# EVmulator_T85_Compact.net
KiCad netlist of a schematic drawn in EAGLE
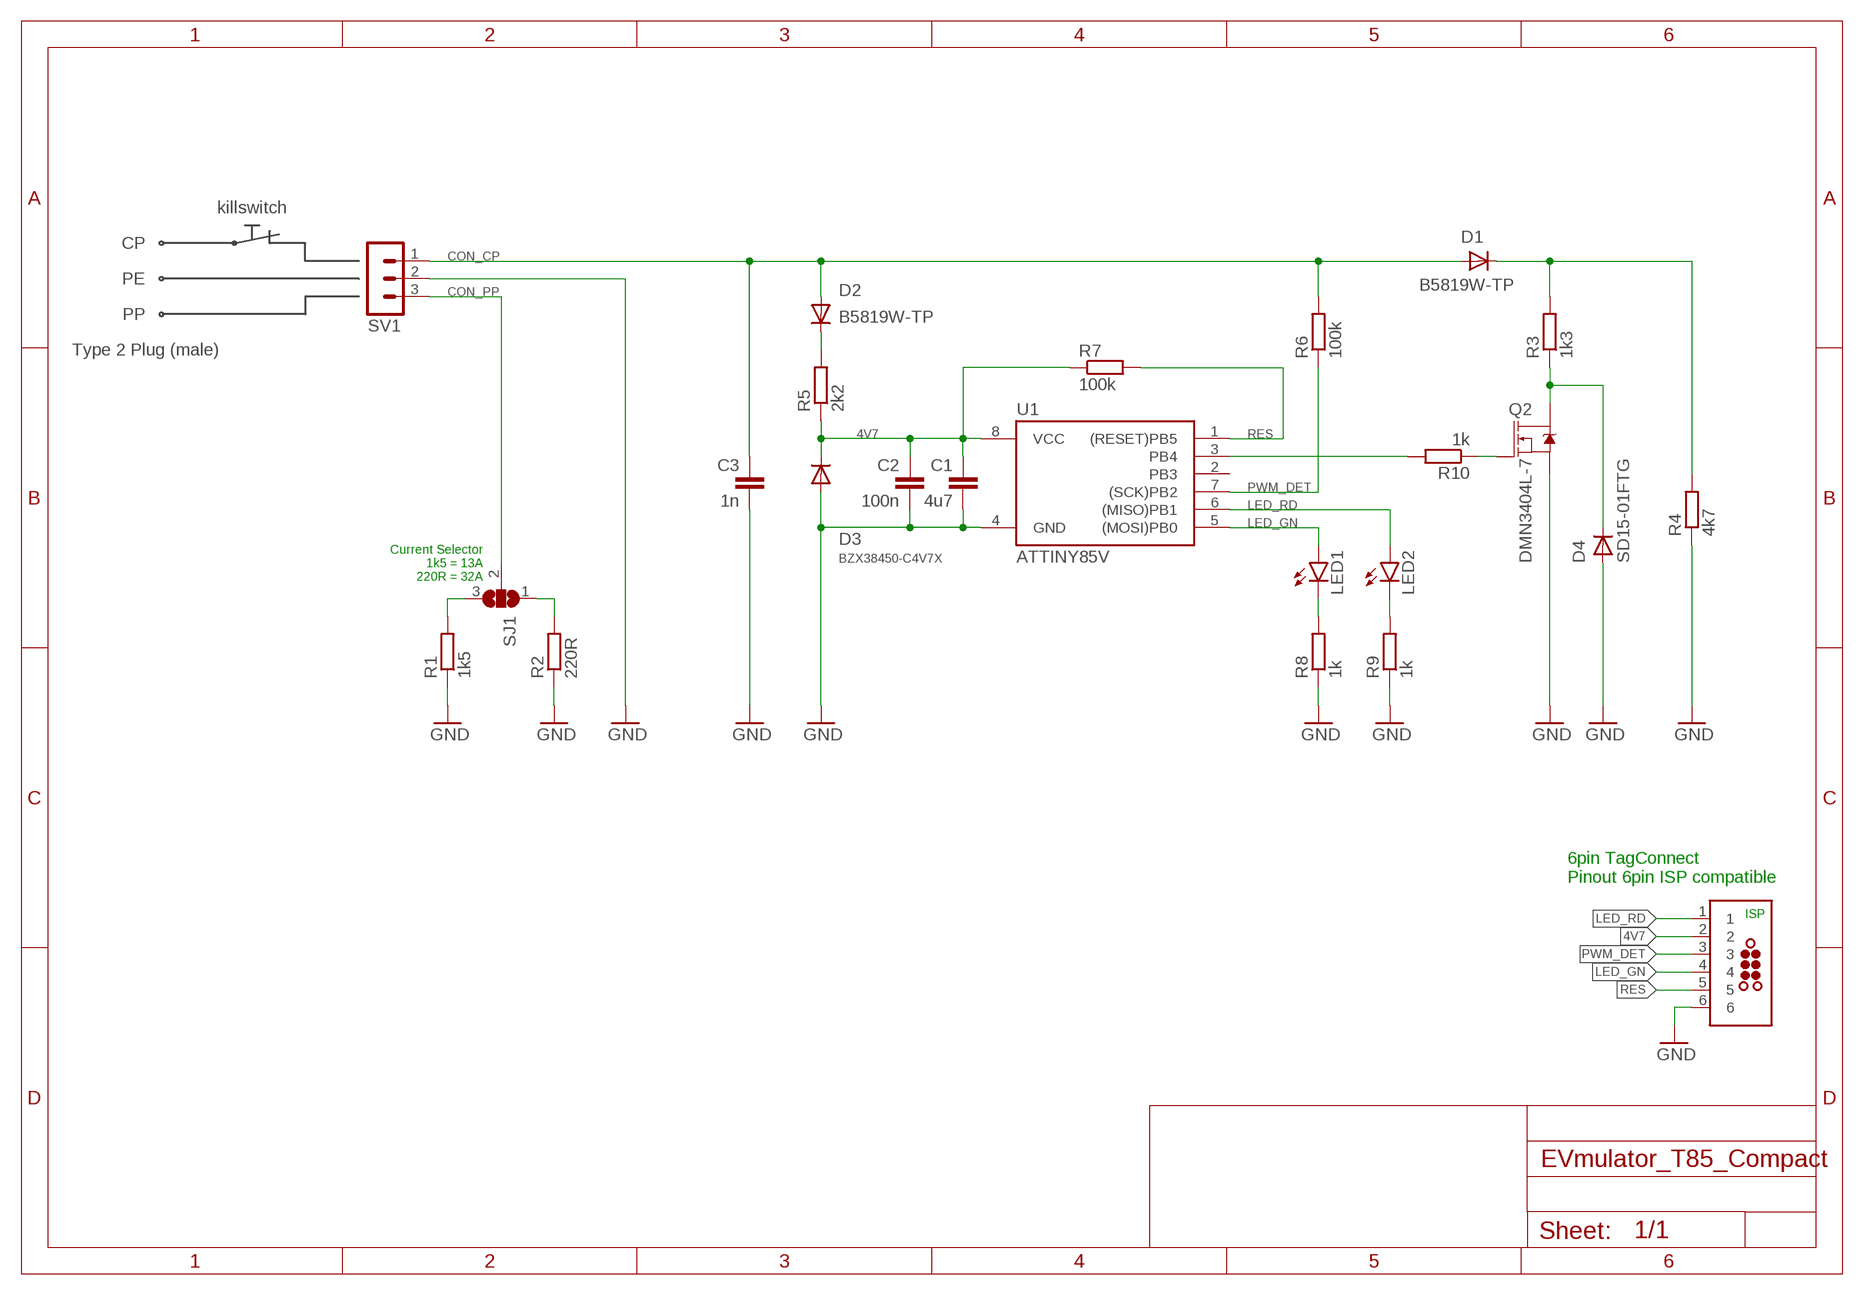
[diagram p0: schematic, sheet 1]

(export (version "E")
  (design (tool "Eeschema 10.0.6"))
  (components
    (comp (ref "C1")
      (value "4u7")
      (footprint "eagle-import:C0603")
      (libsource (lib "eagle-import") (part "C-EUC0603"))
    )
    (comp (ref "C2")
      (value "100n")
      (footprint "eagle-import:C0603")
      (libsource (lib "eagle-import") (part "C-EUC0603"))
    )
    (comp (ref "C3")
      (value "1n")
      (footprint "eagle-import:C0603")
      (libsource (lib "eagle-import") (part "C-EUC0603"))
    )
    (comp (ref "D1")
      (value "B5819W-TP")
      (footprint "eagle-import:SOD-123")
      (libsource (lib "eagle-import") (part "DIODESOD-123"))
    )
    (comp (ref "D2")
      (value "B5819W-TP")
      (footprint "eagle-import:SOD-123")
      (libsource (lib "eagle-import") (part "DIODESOD-123"))
    )
    (comp (ref "D3")
      (value "BZX38450-C4V7X")
      (footprint "eagle-import:SOD-323F")
      (libsource (lib "eagle-import") (part "DIODESOD-323F"))
    )
    (comp (ref "D4")
      (value "SD15-01FTG")
      (footprint "eagle-import:SOD-323F")
      (libsource (lib "eagle-import") (part "DIODESOD-323F"))
    )
    (comp (ref "J1")
      (value "TAG-CONNECT_TC2030-MCP-NL")
      (footprint "eagle-import:TAG-CONNECT_TC2030-MCP-NL")
      (libsource (lib "eagle-import") (part "TAG-CONNECT_TC2030-MCP-NL"))
    )
    (comp (ref "LED1")
      (value "LEDCHIP-LED0603")
      (footprint "eagle-import:CHIP-LED0603")
      (libsource (lib "eagle-import") (part "LEDCHIP-LED0603"))
    )
    (comp (ref "LED2")
      (value "LEDCHIP-LED0603")
      (footprint "eagle-import:CHIP-LED0603")
      (libsource (lib "eagle-import") (part "LEDCHIP-LED0603"))
    )
    (comp (ref "Q2")
      (value "DMN3404L-7")
      (footprint "eagle-import:SOT23-3")
      (libsource (lib "eagle-import") (part "MOSFET-NCH-AO3404A"))
    )
    (comp (ref "R1")
      (value "1k5")
      (footprint "eagle-import:R0805")
      (libsource (lib "eagle-import") (part "R-EU_R0805"))
    )
    (comp (ref "R2")
      (value "220R")
      (footprint "eagle-import:R0805")
      (libsource (lib "eagle-import") (part "R-EU_R0805"))
    )
    (comp (ref "R3")
      (value "1k3")
      (footprint "eagle-import:R0603")
      (libsource (lib "eagle-import") (part "R-EU_R0603"))
    )
    (comp (ref "R4")
      (value "4k7")
      (footprint "eagle-import:R0603")
      (libsource (lib "eagle-import") (part "R-EU_R0603"))
    )
    (comp (ref "R5")
      (value "2k2")
      (footprint "eagle-import:R0603")
      (libsource (lib "eagle-import") (part "R-EU_R0603"))
    )
    (comp (ref "R6")
      (value "100k")
      (footprint "eagle-import:R0603")
      (libsource (lib "eagle-import") (part "R-EU_R0603"))
    )
    (comp (ref "R7")
      (value "100k")
      (footprint "eagle-import:R0603")
      (libsource (lib "eagle-import") (part "R-EU_R0603"))
    )
    (comp (ref "R8")
      (value "1k")
      (footprint "eagle-import:R0603")
      (libsource (lib "eagle-import") (part "R-EU_R0603"))
    )
    (comp (ref "R9")
      (value "1k")
      (footprint "eagle-import:R0603")
      (libsource (lib "eagle-import") (part "R-EU_R0603"))
    )
    (comp (ref "R10")
      (value "1k")
      (footprint "eagle-import:R0603")
      (libsource (lib "eagle-import") (part "R-EU_R0603"))
    )
    (comp (ref "SJ1")
      (value "SJ2W")
      (footprint "eagle-import:SJ_2")
      (libsource (lib "eagle-import") (part "SJ2W"))
    )
    (comp (ref "SV1")
      (value "MA03-1")
      (footprint "eagle-import:MA03-1")
      (libsource (lib "eagle-import") (part "MA03-1"))
    )
    (comp (ref "U1")
      (value "ATTINY85V")
      (footprint "eagle-import:SOIC8")
      (libsource (lib "eagle-import") (part "ATTINY25/45/85-20SU"))
    )
  )
  (nets
    (net (code "1") (name "/CON_CP") (class "Default")
      (node (ref "C3") (pin "1") (pinfunction "1_1") (pintype "passive"))
      (node (ref "D1") (pin "A") (pinfunction "A_A") (pintype "passive"))
      (node (ref "D2") (pin "A") (pinfunction "A_A") (pintype "passive"))
      (node (ref "R6") (pin "2") (pinfunction "2_2") (pintype "passive"))
      (node (ref "SV1") (pin "1") (pinfunction "1_1") (pintype "passive"))
    )
    (net (code "2") (name "/CON_PP") (class "Default")
      (node (ref "SJ1") (pin "2") (pinfunction "2_2") (pintype "passive"))
      (node (ref "SV1") (pin "3") (pinfunction "3_3") (pintype "passive"))
    )
    (net (code "3") (name "4V7") (class "Default")
      (node (ref "C1") (pin "1") (pinfunction "1_1") (pintype "passive"))
      (node (ref "C2") (pin "1") (pinfunction "1_1") (pintype "passive"))
      (node (ref "D3") (pin "C") (pinfunction "C_C") (pintype "passive"))
      (node (ref "J1") (pin "2") (pinfunction "2_2") (pintype "power_in"))
      (node (ref "R5") (pin "1") (pinfunction "1_1") (pintype "passive"))
      (node (ref "R7") (pin "1") (pinfunction "1_1") (pintype "passive"))
      (node (ref "U1") (pin "8") (pinfunction "VCC_8") (pintype "power_in"))
    )
    (net (code "4") (name "GND") (class "Default")
      (node (ref "C1") (pin "2") (pinfunction "2_2") (pintype "passive"))
      (node (ref "C2") (pin "2") (pinfunction "2_2") (pintype "passive"))
      (node (ref "C3") (pin "2") (pinfunction "2_2") (pintype "passive"))
      (node (ref "D3") (pin "A") (pinfunction "A_A") (pintype "passive"))
      (node (ref "D4") (pin "A") (pinfunction "A_A") (pintype "passive"))
      (node (ref "J1") (pin "6") (pinfunction "6_6") (pintype "bidirectional"))
      (node (ref "Q2") (pin "2") (pinfunction "S_2") (pintype "bidirectional"))
      (node (ref "R1") (pin "1") (pinfunction "1_1") (pintype "passive"))
      (node (ref "R2") (pin "1") (pinfunction "1_1") (pintype "passive"))
      (node (ref "R4") (pin "1") (pinfunction "1_1") (pintype "passive"))
      (node (ref "R8") (pin "1") (pinfunction "1_1") (pintype "passive"))
      (node (ref "R9") (pin "1") (pinfunction "1_1") (pintype "passive"))
      (node (ref "SV1") (pin "2") (pinfunction "2_2") (pintype "passive"))
      (node (ref "U1") (pin "4") (pinfunction "GND_4") (pintype "power_in"))
    )
    (net (code "5") (name "LED_GN") (class "Default")
      (node (ref "J1") (pin "4") (pinfunction "4_4") (pintype "bidirectional"))
      (node (ref "LED1") (pin "A") (pinfunction "A_A") (pintype "passive"))
      (node (ref "U1") (pin "5") (pinfunction "(MOSI)PB0_5") (pintype "bidirectional"))
    )
    (net (code "6") (name "LED_RD") (class "Default")
      (node (ref "J1") (pin "1") (pinfunction "1_1") (pintype "passive"))
      (node (ref "LED2") (pin "A") (pinfunction "A_A") (pintype "passive"))
      (node (ref "U1") (pin "6") (pinfunction "(MISO)PB1_6") (pintype "bidirectional"))
    )
    (net (code "7") (name "Net-(D1-PadC)") (class "Default")
      (node (ref "D1") (pin "C") (pinfunction "C_C") (pintype "passive"))
      (node (ref "R3") (pin "2") (pinfunction "2_2") (pintype "passive"))
      (node (ref "R4") (pin "2") (pinfunction "2_2") (pintype "passive"))
    )
    (net (code "8") (name "Net-(D2-PadC)") (class "Default")
      (node (ref "D2") (pin "C") (pinfunction "C_C") (pintype "passive"))
      (node (ref "R5") (pin "2") (pinfunction "2_2") (pintype "passive"))
    )
    (net (code "9") (name "Net-(LED1-PadC)") (class "Default")
      (node (ref "LED1") (pin "C") (pinfunction "C_C") (pintype "passive"))
      (node (ref "R8") (pin "2") (pinfunction "2_2") (pintype "passive"))
    )
    (net (code "10") (name "Net-(LED2-PadC)") (class "Default")
      (node (ref "LED2") (pin "C") (pinfunction "C_C") (pintype "passive"))
      (node (ref "R9") (pin "2") (pinfunction "2_2") (pintype "passive"))
    )
    (net (code "11") (name "Net-(Q2-D)") (class "Default")
      (node (ref "D4") (pin "C") (pinfunction "C_C") (pintype "passive"))
      (node (ref "Q2") (pin "3") (pinfunction "D_3") (pintype "bidirectional"))
      (node (ref "R3") (pin "1") (pinfunction "1_1") (pintype "passive"))
    )
    (net (code "12") (name "Net-(Q2-G)") (class "Default")
      (node (ref "Q2") (pin "1") (pinfunction "G_1") (pintype "bidirectional"))
      (node (ref "R10") (pin "1") (pinfunction "1_1") (pintype "passive"))
    )
    (net (code "13") (name "Net-(R1-Pad2)") (class "Default")
      (node (ref "R1") (pin "2") (pinfunction "2_2") (pintype "passive"))
      (node (ref "SJ1") (pin "3") (pinfunction "3_3") (pintype "passive"))
    )
    (net (code "14") (name "Net-(R2-Pad2)") (class "Default")
      (node (ref "R2") (pin "2") (pinfunction "2_2") (pintype "passive"))
      (node (ref "SJ1") (pin "1") (pinfunction "1_1") (pintype "passive"))
    )
    (net (code "15") (name "Net-(U1-PB4)") (class "Default")
      (node (ref "R10") (pin "2") (pinfunction "2_2") (pintype "passive"))
      (node (ref "U1") (pin "3") (pinfunction "PB4_3") (pintype "bidirectional"))
    )
    (net (code "16") (name "PWM_DET") (class "Default")
      (node (ref "J1") (pin "3") (pinfunction "3_3") (pintype "power_in"))
      (node (ref "R6") (pin "1") (pinfunction "1_1") (pintype "passive"))
      (node (ref "U1") (pin "7") (pinfunction "(SCK)PB2_7") (pintype "bidirectional"))
    )
    (net (code "17") (name "RES") (class "Default")
      (node (ref "J1") (pin "5") (pinfunction "5_5") (pintype "output"))
      (node (ref "R7") (pin "2") (pinfunction "2_2") (pintype "passive"))
      (node (ref "U1") (pin "1") (pinfunction "(RESET)PB5_1") (pintype "bidirectional"))
    )
    (net (code "18") (name "unconnected-(U1-PB3-Pad2)") (class "Default")
      (node (ref "U1") (pin "2") (pinfunction "PB3_2") (pintype "bidirectional"))
    )
  )
)
